# psu.net
KiCad netlist of a schematic drawn in EAGLE
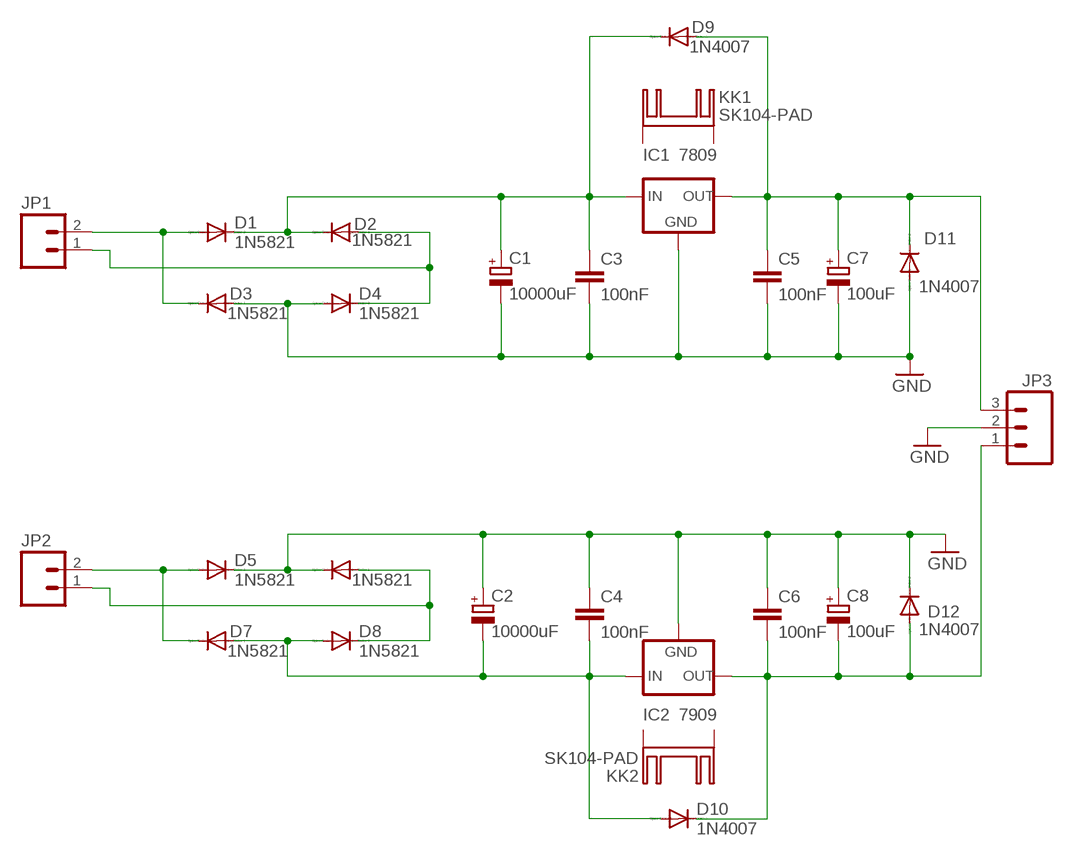
[diagram p0: schematic, sheet 1]

(export (version "E")
  (design (tool "Eeschema 10.0.6"))
  (components
    (comp (ref "C1")
      (value "10000uF")
      (footprint "eagle-import:E7,5-18")
      (libsource (lib "eagle-import") (part "CPOL-EUE7.5-18"))
    )
    (comp (ref "C2")
      (value "10000uF")
      (footprint "eagle-import:E7,5-18")
      (libsource (lib "eagle-import") (part "CPOL-EUE7.5-18"))
    )
    (comp (ref "C3")
      (value "100nF")
      (footprint "eagle-import:C025-025X050")
      (libsource (lib "eagle-import") (part "C-EU025-025X050"))
    )
    (comp (ref "C4")
      (value "100nF")
      (footprint "eagle-import:C025-025X050")
      (libsource (lib "eagle-import") (part "C-EU025-025X050"))
    )
    (comp (ref "C5")
      (value "100nF")
      (footprint "eagle-import:C025-025X050")
      (libsource (lib "eagle-import") (part "C-EU025-025X050"))
    )
    (comp (ref "C6")
      (value "100nF")
      (footprint "eagle-import:C025-025X050")
      (libsource (lib "eagle-import") (part "C-EU025-025X050"))
    )
    (comp (ref "C7")
      (value "100uF")
      (footprint "eagle-import:E2,5-7")
      (libsource (lib "eagle-import") (part "CPOL-EUE2.5-7"))
    )
    (comp (ref "C8")
      (value "100uF")
      (footprint "eagle-import:E2,5-7")
      (libsource (lib "eagle-import") (part "CPOL-EUE2.5-7"))
    )
    (comp (ref "D1")
      (value "1N5821")
      (footprint "eagle-import:DO201-15")
      (libsource (lib "eagle-import") (part "1N5821"))
    )
    (comp (ref "D2")
      (value "1N5821")
      (footprint "eagle-import:DO201-15")
      (libsource (lib "eagle-import") (part "1N5821"))
    )
    (comp (ref "D3")
      (value "1N5821")
      (footprint "eagle-import:DO201-15")
      (libsource (lib "eagle-import") (part "1N5821"))
    )
    (comp (ref "D4")
      (value "1N5821")
      (footprint "eagle-import:DO201-15")
      (libsource (lib "eagle-import") (part "1N5821"))
    )
    (comp (ref "D5")
      (value "1N5821")
      (footprint "eagle-import:DO201-15")
      (libsource (lib "eagle-import") (part "1N5821"))
    )
    (comp (ref "D6")
      (value "1N5821")
      (footprint "eagle-import:DO201-15")
      (libsource (lib "eagle-import") (part "1N5821"))
    )
    (comp (ref "D7")
      (value "1N5821")
      (footprint "eagle-import:DO201-15")
      (libsource (lib "eagle-import") (part "1N5821"))
    )
    (comp (ref "D8")
      (value "1N5821")
      (footprint "eagle-import:DO201-15")
      (libsource (lib "eagle-import") (part "1N5821"))
    )
    (comp (ref "D9")
      (value "1N4007")
      (footprint "eagle-import:DO41-10")
      (libsource (lib "eagle-import") (part "1N4007"))
    )
    (comp (ref "D10")
      (value "1N4007")
      (footprint "eagle-import:DO41-10")
      (libsource (lib "eagle-import") (part "1N4007"))
    )
    (comp (ref "D11")
      (value "1N4007")
      (footprint "eagle-import:DO41-10")
      (libsource (lib "eagle-import") (part "1N4007"))
    )
    (comp (ref "D12")
      (value "1N4007")
      (footprint "eagle-import:DO41-10")
      (libsource (lib "eagle-import") (part "1N4007"))
    )
    (comp (ref "IC1")
      (value "7809")
      (footprint "eagle-import:78XXS")
      (libsource (lib "eagle-import") (part "78XXS"))
    )
    (comp (ref "IC2")
      (value "7909")
      (footprint "eagle-import:79XXS")
      (libsource (lib "eagle-import") (part "79XXS"))
    )
    (comp (ref "JP1")
      (value "M025MM")
      (footprint "eagle-import:SCREWTERMINAL-5MM-2")
      (libsource (lib "eagle-import") (part "M025MM"))
    )
    (comp (ref "JP2")
      (value "M025MM")
      (footprint "eagle-import:SCREWTERMINAL-5MM-2")
      (libsource (lib "eagle-import") (part "M025MM"))
    )
    (comp (ref "JP3")
      (value "M03-SCREW-5MM")
      (footprint "eagle-import:SCREWTERMINAL-5MM-3")
      (libsource (lib "eagle-import") (part "M03-SCREW-5MM"))
    )
    (comp (ref "KK1")
      (value "SK104-PAD")
      (footprint "eagle-import:SK104-PAD")
      (libsource (lib "eagle-import") (part "SK104-PAD"))
    )
    (comp (ref "KK2")
      (value "SK104-PAD")
      (footprint "eagle-import:SK104-PAD")
      (libsource (lib "eagle-import") (part "SK104-PAD"))
    )
  )
  (nets
    (net (code "1") (name "GND") (class "Default")
      (node (ref "C1") (pin "-") (pinfunction "-_-") (pintype "passive"))
      (node (ref "C2") (pin "+") (pinfunction "+_+") (pintype "passive"))
      (node (ref "C3") (pin "2") (pinfunction "2_2") (pintype "passive"))
      (node (ref "C4") (pin "1") (pinfunction "1_1") (pintype "passive"))
      (node (ref "C5") (pin "2") (pinfunction "2_2") (pintype "passive"))
      (node (ref "C6") (pin "1") (pinfunction "1_1") (pintype "passive"))
      (node (ref "C7") (pin "-") (pinfunction "-_-") (pintype "passive"))
      (node (ref "C8") (pin "+") (pinfunction "+_+") (pintype "passive"))
      (node (ref "D11") (pin "A") (pinfunction "A_A") (pintype "passive"))
      (node (ref "D12") (pin "C") (pinfunction "C_C") (pintype "passive"))
      (node (ref "D3") (pin "A") (pinfunction "A_A") (pintype "passive"))
      (node (ref "D4") (pin "A") (pinfunction "A_A") (pintype "passive"))
      (node (ref "D5") (pin "C") (pinfunction "C_C") (pintype "passive"))
      (node (ref "D6") (pin "C") (pinfunction "C_C") (pintype "passive"))
      (node (ref "IC1") (pin "GND") (pinfunction "GND_GND") (pintype "input"))
      (node (ref "IC2") (pin "GND") (pinfunction "GND_GND") (pintype "input"))
      (node (ref "JP3") (pin "2") (pinfunction "2_2") (pintype "passive"))
    )
    (net (code "2") (name "Net-(C1-Pad+)") (class "Default")
      (node (ref "C1") (pin "+") (pinfunction "+_+") (pintype "passive"))
      (node (ref "C3") (pin "1") (pinfunction "1_1") (pintype "passive"))
      (node (ref "D1") (pin "C") (pinfunction "C_C") (pintype "passive"))
      (node (ref "D2") (pin "C") (pinfunction "C_C") (pintype "passive"))
      (node (ref "D9") (pin "C") (pinfunction "C_C") (pintype "passive"))
      (node (ref "IC1") (pin "IN") (pinfunction "IN_IN") (pintype "input"))
    )
    (net (code "3") (name "Net-(C2-Pad-)") (class "Default")
      (node (ref "C2") (pin "-") (pinfunction "-_-") (pintype "passive"))
      (node (ref "C4") (pin "2") (pinfunction "2_2") (pintype "passive"))
      (node (ref "D10") (pin "A") (pinfunction "A_A") (pintype "passive"))
      (node (ref "D7") (pin "A") (pinfunction "A_A") (pintype "passive"))
      (node (ref "D8") (pin "A") (pinfunction "A_A") (pintype "passive"))
      (node (ref "IC2") (pin "IN") (pinfunction "IN_IN") (pintype "input"))
    )
    (net (code "4") (name "Net-(C5-Pad1)") (class "Default")
      (node (ref "C5") (pin "1") (pinfunction "1_1") (pintype "passive"))
      (node (ref "C7") (pin "+") (pinfunction "+_+") (pintype "passive"))
      (node (ref "D11") (pin "C") (pinfunction "C_C") (pintype "passive"))
      (node (ref "D9") (pin "A") (pinfunction "A_A") (pintype "passive"))
      (node (ref "IC1") (pin "OUT") (pinfunction "OUT_OUT") (pintype "passive"))
      (node (ref "JP3") (pin "3") (pinfunction "3_3") (pintype "passive"))
    )
    (net (code "5") (name "Net-(C6-Pad2)") (class "Default")
      (node (ref "C6") (pin "2") (pinfunction "2_2") (pintype "passive"))
      (node (ref "C8") (pin "-") (pinfunction "-_-") (pintype "passive"))
      (node (ref "D10") (pin "C") (pinfunction "C_C") (pintype "passive"))
      (node (ref "D12") (pin "A") (pinfunction "A_A") (pintype "passive"))
      (node (ref "IC2") (pin "OUT") (pinfunction "OUT_OUT") (pintype "passive"))
      (node (ref "JP3") (pin "1") (pinfunction "1_1") (pintype "passive"))
    )
    (net (code "6") (name "Net-(D1-PadA)") (class "Default")
      (node (ref "D1") (pin "A") (pinfunction "A_A") (pintype "passive"))
      (node (ref "D3") (pin "C") (pinfunction "C_C") (pintype "passive"))
      (node (ref "JP1") (pin "2") (pinfunction "2_2") (pintype "passive"))
    )
    (net (code "7") (name "Net-(D2-PadA)") (class "Default")
      (node (ref "D2") (pin "A") (pinfunction "A_A") (pintype "passive"))
      (node (ref "D4") (pin "C") (pinfunction "C_C") (pintype "passive"))
      (node (ref "JP1") (pin "1") (pinfunction "1_1") (pintype "passive"))
    )
    (net (code "8") (name "Net-(D5-PadA)") (class "Default")
      (node (ref "D5") (pin "A") (pinfunction "A_A") (pintype "passive"))
      (node (ref "D7") (pin "C") (pinfunction "C_C") (pintype "passive"))
      (node (ref "JP2") (pin "2") (pinfunction "2_2") (pintype "passive"))
    )
    (net (code "9") (name "Net-(D6-PadA)") (class "Default")
      (node (ref "D6") (pin "A") (pinfunction "A_A") (pintype "passive"))
      (node (ref "D8") (pin "C") (pinfunction "C_C") (pintype "passive"))
      (node (ref "JP2") (pin "1") (pinfunction "1_1") (pintype "passive"))
    )
    (net (code "10") (name "unconnected-(KK1-K-PadK1)") (class "Default")
      (node (ref "KK1") (pin "K1") (pinfunction "K_K1") (pintype "passive"))
    )
    (net (code "11") (name "unconnected-(KK1-K-PadK2)") (class "Default")
      (node (ref "KK1") (pin "K2") (pinfunction "K_K2") (pintype "passive"))
    )
    (net (code "12") (name "unconnected-(KK2-K-PadK1)") (class "Default")
      (node (ref "KK2") (pin "K1") (pinfunction "K_K1") (pintype "passive"))
    )
    (net (code "13") (name "unconnected-(KK2-K-PadK2)") (class "Default")
      (node (ref "KK2") (pin "K2") (pinfunction "K_K2") (pintype "passive"))
    )
  )
)
